# template.net
KiCad netlist of a schematic drawn in EAGLE
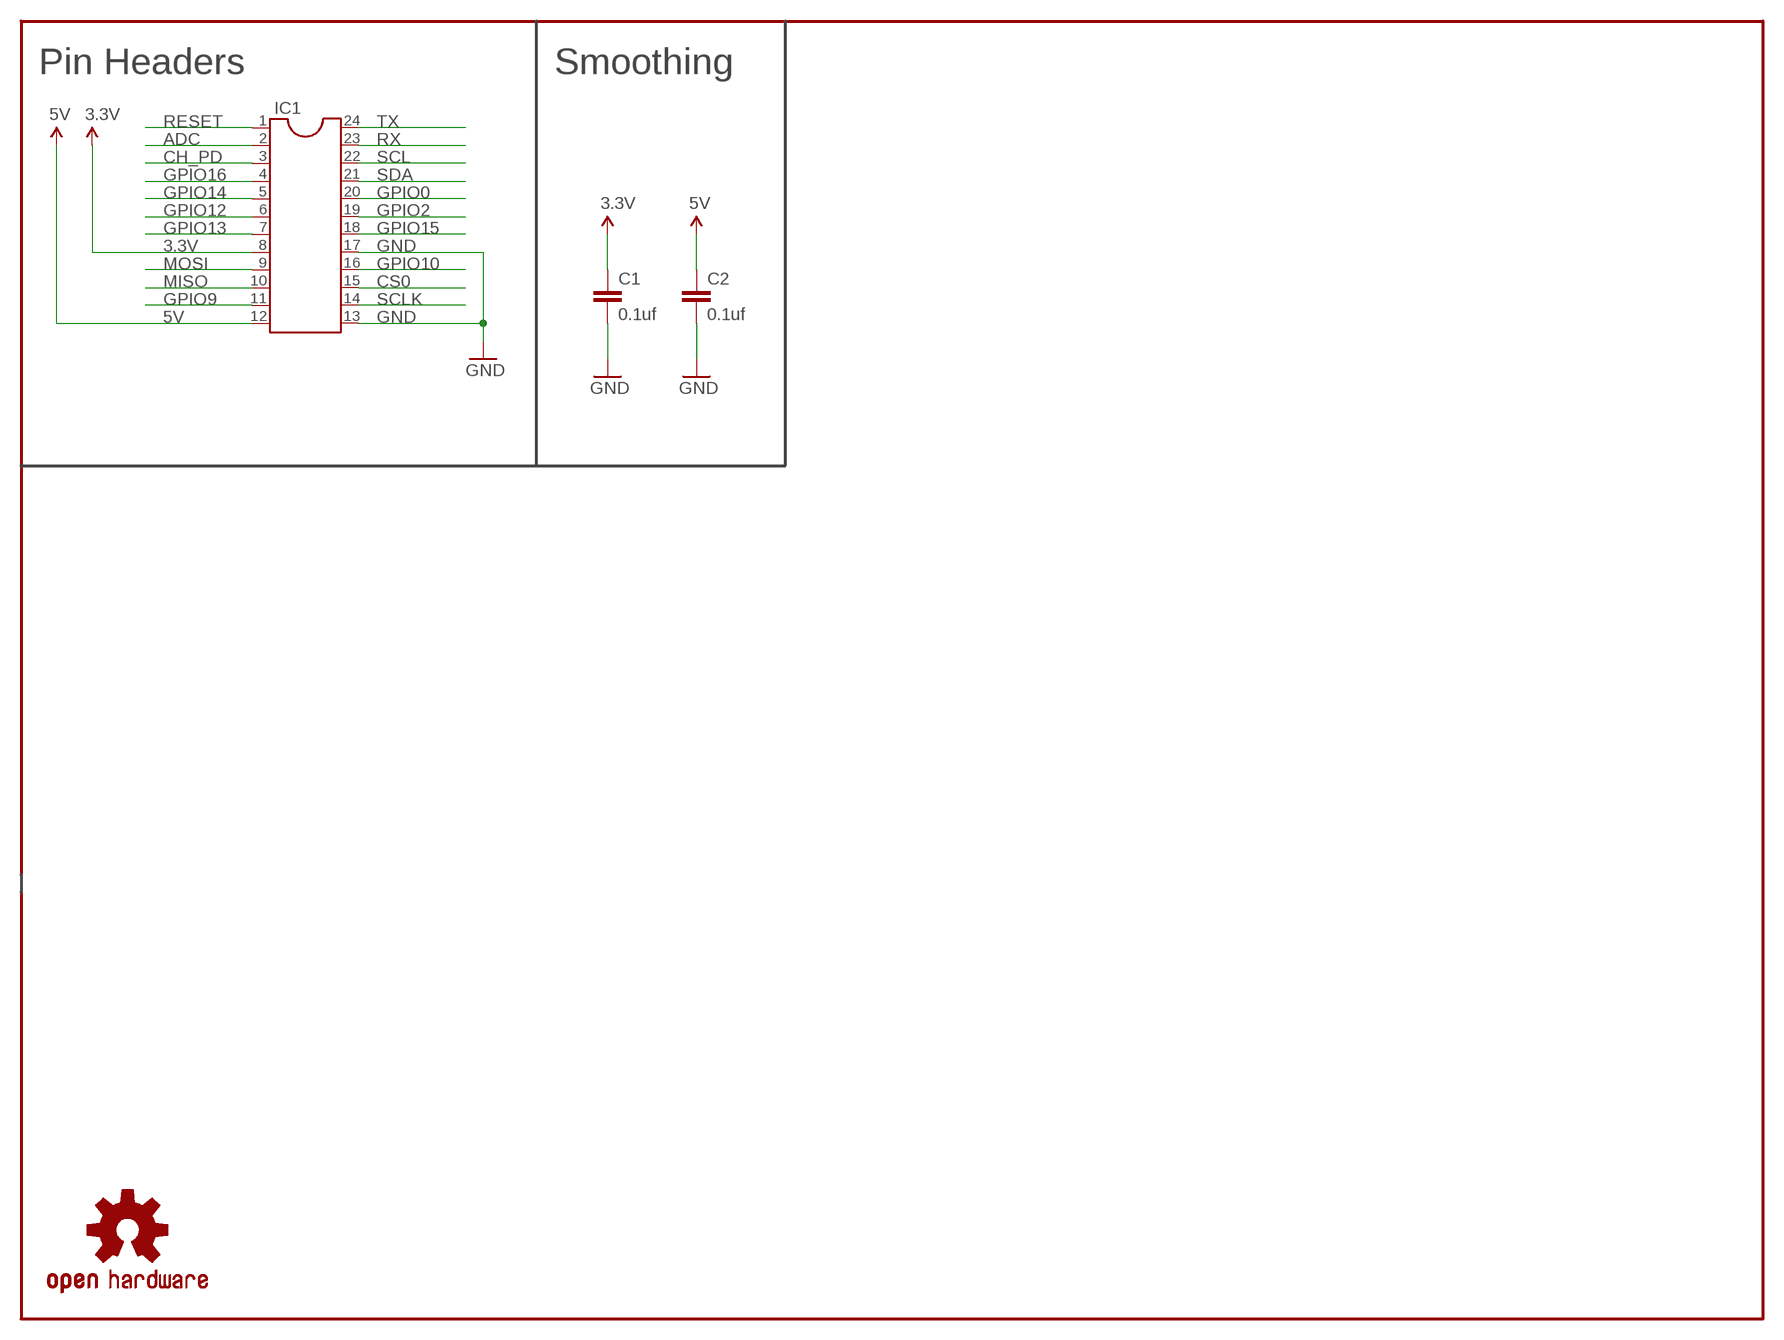
[diagram p0: schematic, sheet 1]

(export (version "E")
  (design (tool "Eeschema 10.0.6"))
  (components
    (comp (ref "C1")
      (value "0.1uf")
      (footprint "eagle-import:1206")
      (libsource (lib "eagle-import") (part "CAP1206"))
    )
    (comp (ref "C2")
      (value "0.1uf")
      (footprint "eagle-import:1206")
      (libsource (lib "eagle-import") (part "CAP1206"))
    )
    (comp (ref "FRAME1")
      (value "FRAME-LETTERNO_PACKAGE")
      (footprint "eagle-import:DUMMY")
      (fields (field (name "DESIGNER") "Nobody"))
      (libsource (lib "eagle-import") (part "FRAME-LETTERNO_PACKAGE"))
    )
    (comp (ref "IC1")
      (value "DIL24-9")
      (footprint "eagle-import:DIL24-9")
      (libsource (lib "eagle-import") (part "DIL24-9"))
    )
    (comp (ref "LOGO1")
      (value "OSHW-LOGOS")
      (footprint "eagle-import:OSHW-LOGO-S")
      (libsource (lib "eagle-import") (part "OSHW-LOGOS"))
    )
  )
  (nets
    (net (code "1") (name "/ADC") (class "Default")
      (node (ref "IC1") (pin "2") (pinfunction "2_2") (pintype "passive"))
    )
    (net (code "2") (name "/CH_PD") (class "Default")
      (node (ref "IC1") (pin "3") (pinfunction "3_3") (pintype "passive"))
    )
    (net (code "3") (name "/CS0") (class "Default")
      (node (ref "IC1") (pin "15") (pinfunction "15_15") (pintype "passive"))
    )
    (net (code "4") (name "/GPIO0") (class "Default")
      (node (ref "IC1") (pin "20") (pinfunction "20_20") (pintype "passive"))
    )
    (net (code "5") (name "/GPIO2") (class "Default")
      (node (ref "IC1") (pin "19") (pinfunction "19_19") (pintype "passive"))
    )
    (net (code "6") (name "/GPIO9") (class "Default")
      (node (ref "IC1") (pin "11") (pinfunction "11_11") (pintype "passive"))
    )
    (net (code "7") (name "/GPIO10") (class "Default")
      (node (ref "IC1") (pin "16") (pinfunction "16_16") (pintype "passive"))
    )
    (net (code "8") (name "/GPIO12") (class "Default")
      (node (ref "IC1") (pin "6") (pinfunction "6_6") (pintype "passive"))
    )
    (net (code "9") (name "/GPIO13") (class "Default")
      (node (ref "IC1") (pin "7") (pinfunction "7_7") (pintype "passive"))
    )
    (net (code "10") (name "/GPIO14") (class "Default")
      (node (ref "IC1") (pin "5") (pinfunction "5_5") (pintype "passive"))
    )
    (net (code "11") (name "/GPIO15") (class "Default")
      (node (ref "IC1") (pin "18") (pinfunction "18_18") (pintype "passive"))
    )
    (net (code "12") (name "/GPIO16") (class "Default")
      (node (ref "IC1") (pin "4") (pinfunction "4_4") (pintype "passive"))
    )
    (net (code "13") (name "/MISO") (class "Default")
      (node (ref "IC1") (pin "10") (pinfunction "10_10") (pintype "passive"))
    )
    (net (code "14") (name "/MOSI") (class "Default")
      (node (ref "IC1") (pin "9") (pinfunction "9_9") (pintype "passive"))
    )
    (net (code "15") (name "/RESET") (class "Default")
      (node (ref "IC1") (pin "1") (pinfunction "1_1") (pintype "passive"))
    )
    (net (code "16") (name "/RX") (class "Default")
      (node (ref "IC1") (pin "23") (pinfunction "23_23") (pintype "passive"))
    )
    (net (code "17") (name "/SCL") (class "Default")
      (node (ref "IC1") (pin "22") (pinfunction "22_22") (pintype "passive"))
    )
    (net (code "18") (name "/SCLK") (class "Default")
      (node (ref "IC1") (pin "14") (pinfunction "14_14") (pintype "passive"))
    )
    (net (code "19") (name "/SDA") (class "Default")
      (node (ref "IC1") (pin "21") (pinfunction "21_21") (pintype "passive"))
    )
    (net (code "20") (name "/TX") (class "Default")
      (node (ref "IC1") (pin "24") (pinfunction "24_24") (pintype "passive"))
    )
    (net (code "21") (name "3.3V") (class "Default")
      (node (ref "C1") (pin "1") (pinfunction "1_1") (pintype "passive"))
      (node (ref "IC1") (pin "8") (pinfunction "8_8") (pintype "passive"))
    )
    (net (code "22") (name "5V") (class "Default")
      (node (ref "C2") (pin "1") (pinfunction "1_1") (pintype "passive"))
      (node (ref "IC1") (pin "12") (pinfunction "12_12") (pintype "passive"))
    )
    (net (code "23") (name "GND") (class "Default")
      (node (ref "C1") (pin "2") (pinfunction "2_2") (pintype "passive"))
      (node (ref "C2") (pin "2") (pinfunction "2_2") (pintype "passive"))
      (node (ref "IC1") (pin "13") (pinfunction "13_13") (pintype "passive"))
      (node (ref "IC1") (pin "17") (pinfunction "17_17") (pintype "passive"))
    )
  )
)
